# mp28164-buck-boost-flashlight-driver-tes.net
KiCad netlist of a schematic drawn in EAGLE
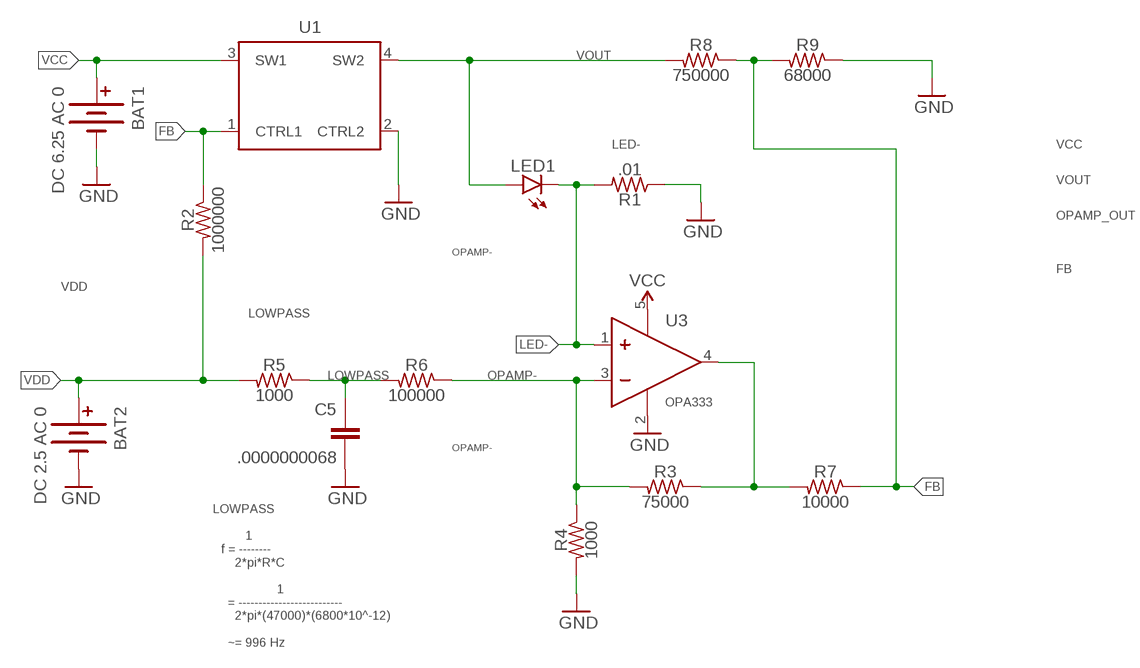
[diagram p0: schematic, sheet 1]

(export (version "E")
  (design (tool "Eeschema 10.0.6"))
  (components
    (comp (ref "BAT1")
      (value "DC 6.25 AC 0")
      (footprint "eagle-import:BATTCON_9V")
      (fields (field (name "SPICEPREFIX") "V"))
      (libsource (lib "eagle-import") (part "BATTERY9V"))
    )
    (comp (ref "BAT2")
      (value "DC 2.5 AC 0")
      (footprint "eagle-import:BATTCON_9V")
      (fields (field (name "SPICEPREFIX") "V"))
      (libsource (lib "eagle-import") (part "BATTERY9V"))
    )
    (comp (ref "C5")
      (value ".0000000068")
      (footprint "eagle-import:C0402")
      (fields (field (name "SPICEPREFIX") "C"))
      (libsource (lib "eagle-import") (part "CAPACITOR-CERAMICC0402"))
    )
    (comp (ref "LED1")
      (value "LED3MM")
      (footprint "eagle-import:LED3MM")
      (fields (field (name "SPICEMODEL") "DMOD") (field (name "SPICEPREFIX") "D"))
      (libsource (lib "eagle-import") (part "LED3MM"))
    )
    (comp (ref "R1")
      (value ".01")
      (footprint "eagle-import:R0805-TIGHTER")
      (fields (field (name "SPICEPREFIX") "R"))
      (libsource (lib "eagle-import") (part "RESISTORR0805-TIGHTER"))
    )
    (comp (ref "R2")
      (value "1000000")
      (footprint "eagle-import:R0402")
      (fields (field (name "SPICEPREFIX") "R"))
      (libsource (lib "eagle-import") (part "RESISTORR0402"))
    )
    (comp (ref "R3")
      (value "75000")
      (footprint "eagle-import:R0402")
      (fields (field (name "SPICEPREFIX") "R"))
      (libsource (lib "eagle-import") (part "RESISTORR0402"))
    )
    (comp (ref "R4")
      (value "1000")
      (footprint "eagle-import:R0402")
      (fields (field (name "SPICEPREFIX") "R"))
      (libsource (lib "eagle-import") (part "RESISTORR0402"))
    )
    (comp (ref "R5")
      (value "1000")
      (footprint "eagle-import:R0402")
      (fields (field (name "SPICEPREFIX") "R"))
      (libsource (lib "eagle-import") (part "RESISTORR0402"))
    )
    (comp (ref "R6")
      (value "100000")
      (footprint "eagle-import:R0402")
      (fields (field (name "SPICEPREFIX") "R"))
      (libsource (lib "eagle-import") (part "RESISTORR0402"))
    )
    (comp (ref "R7")
      (value "10000")
      (footprint "eagle-import:R0402")
      (fields (field (name "SPICEPREFIX") "R"))
      (libsource (lib "eagle-import") (part "RESISTORR0402"))
    )
    (comp (ref "R8")
      (value "750000")
      (footprint "eagle-import:R0402")
      (fields (field (name "SPICEPREFIX") "R"))
      (libsource (lib "eagle-import") (part "RESISTORR0402"))
    )
    (comp (ref "R9")
      (value "68000")
      (footprint "eagle-import:R0402")
      (fields (field (name "SPICEPREFIX") "R"))
      (libsource (lib "eagle-import") (part "RESISTORR0402"))
    )
    (comp (ref "U1")
      (value "VSWITCH")
      (footprint "eagle-import:DIL04")
      (fields (field (name "SPICEMODEL") "VSMOD") (field (name "SPICEPREFIX") "S"))
      (libsource (lib "eagle-import") (part "VSWITCH"))
    )
    (comp (ref "U3")
      (value "OPA333")
      (footprint "eagle-import:SC70")
      (fields (field (name "SPICEMODEL") "OPAMP") (field (name "SPICEPREFIX") "X"))
      (libsource (lib "eagle-import") (part "OPAMPOPA333-SC-70"))
    )
  )
  (nets
    (net (code "1") (name "/LOWPASS") (class "Default")
      (node (ref "C5") (pin "1") (pinfunction "1_1") (pintype "passive"))
      (node (ref "R5") (pin "1") (pinfunction "1_1") (pintype "passive"))
      (node (ref "R6") (pin "2") (pinfunction "2_2") (pintype "passive"))
    )
    (net (code "2") (name "/OPAMP-") (class "Default")
      (node (ref "R3") (pin "2") (pinfunction "2_2") (pintype "passive"))
      (node (ref "R4") (pin "1") (pinfunction "1_1") (pintype "passive"))
      (node (ref "R6") (pin "1") (pinfunction "1_1") (pintype "passive"))
      (node (ref "U3") (pin "3") (pinfunction "IN-_3") (pintype "input"))
    )
    (net (code "3") (name "/VOUT") (class "Default")
      (node (ref "LED1") (pin "A") (pinfunction "A_A") (pintype "passive"))
      (node (ref "R8") (pin "2") (pinfunction "2_2") (pintype "passive"))
      (node (ref "U1") (pin "4") (pinfunction "SW2_4") (pintype "bidirectional"))
    )
    (net (code "4") (name "FB") (class "Default")
      (node (ref "R2") (pin "1") (pinfunction "1_1") (pintype "passive"))
      (node (ref "R7") (pin "1") (pinfunction "1_1") (pintype "passive"))
      (node (ref "R8") (pin "1") (pinfunction "1_1") (pintype "passive"))
      (node (ref "R9") (pin "2") (pinfunction "2_2") (pintype "passive"))
      (node (ref "U1") (pin "1") (pinfunction "CTRL1_1") (pintype "bidirectional"))
    )
    (net (code "5") (name "GND") (class "Default")
      (node (ref "BAT1") (pin "-") (pinfunction "-_-") (pintype "power_in"))
      (node (ref "BAT2") (pin "-") (pinfunction "-_-") (pintype "power_in"))
      (node (ref "C5") (pin "2") (pinfunction "2_2") (pintype "passive"))
      (node (ref "R1") (pin "1") (pinfunction "1_1") (pintype "passive"))
      (node (ref "R4") (pin "2") (pinfunction "2_2") (pintype "passive"))
      (node (ref "R9") (pin "1") (pinfunction "1_1") (pintype "passive"))
      (node (ref "U1") (pin "2") (pinfunction "CTRL2_2") (pintype "bidirectional"))
      (node (ref "U3") (pin "2") (pinfunction "V-_2") (pintype "power_in"))
    )
    (net (code "6") (name "LED-") (class "Default")
      (node (ref "LED1") (pin "K") (pinfunction "C_K") (pintype "passive"))
      (node (ref "R1") (pin "2") (pinfunction "2_2") (pintype "passive"))
      (node (ref "U3") (pin "1") (pinfunction "IN+_1") (pintype "input"))
    )
    (net (code "7") (name "Net-(U3-OUT)") (class "Default")
      (node (ref "R3") (pin "1") (pinfunction "1_1") (pintype "passive"))
      (node (ref "R7") (pin "2") (pinfunction "2_2") (pintype "passive"))
      (node (ref "U3") (pin "4") (pinfunction "OUT_4") (pintype "output"))
    )
    (net (code "8") (name "VCC") (class "Default")
      (node (ref "BAT1") (pin "+") (pinfunction "+_+") (pintype "power_in"))
      (node (ref "U1") (pin "3") (pinfunction "SW1_3") (pintype "bidirectional"))
      (node (ref "U3") (pin "5") (pinfunction "V+_5") (pintype "power_in"))
    )
    (net (code "9") (name "VDD") (class "Default")
      (node (ref "BAT2") (pin "+") (pinfunction "+_+") (pintype "power_in"))
      (node (ref "R2") (pin "2") (pinfunction "2_2") (pintype "passive"))
      (node (ref "R5") (pin "2") (pinfunction "2_2") (pintype "passive"))
    )
  )
)
